# PCB_Blocks.net
KiCad netlist of a schematic drawn in Altium Designer
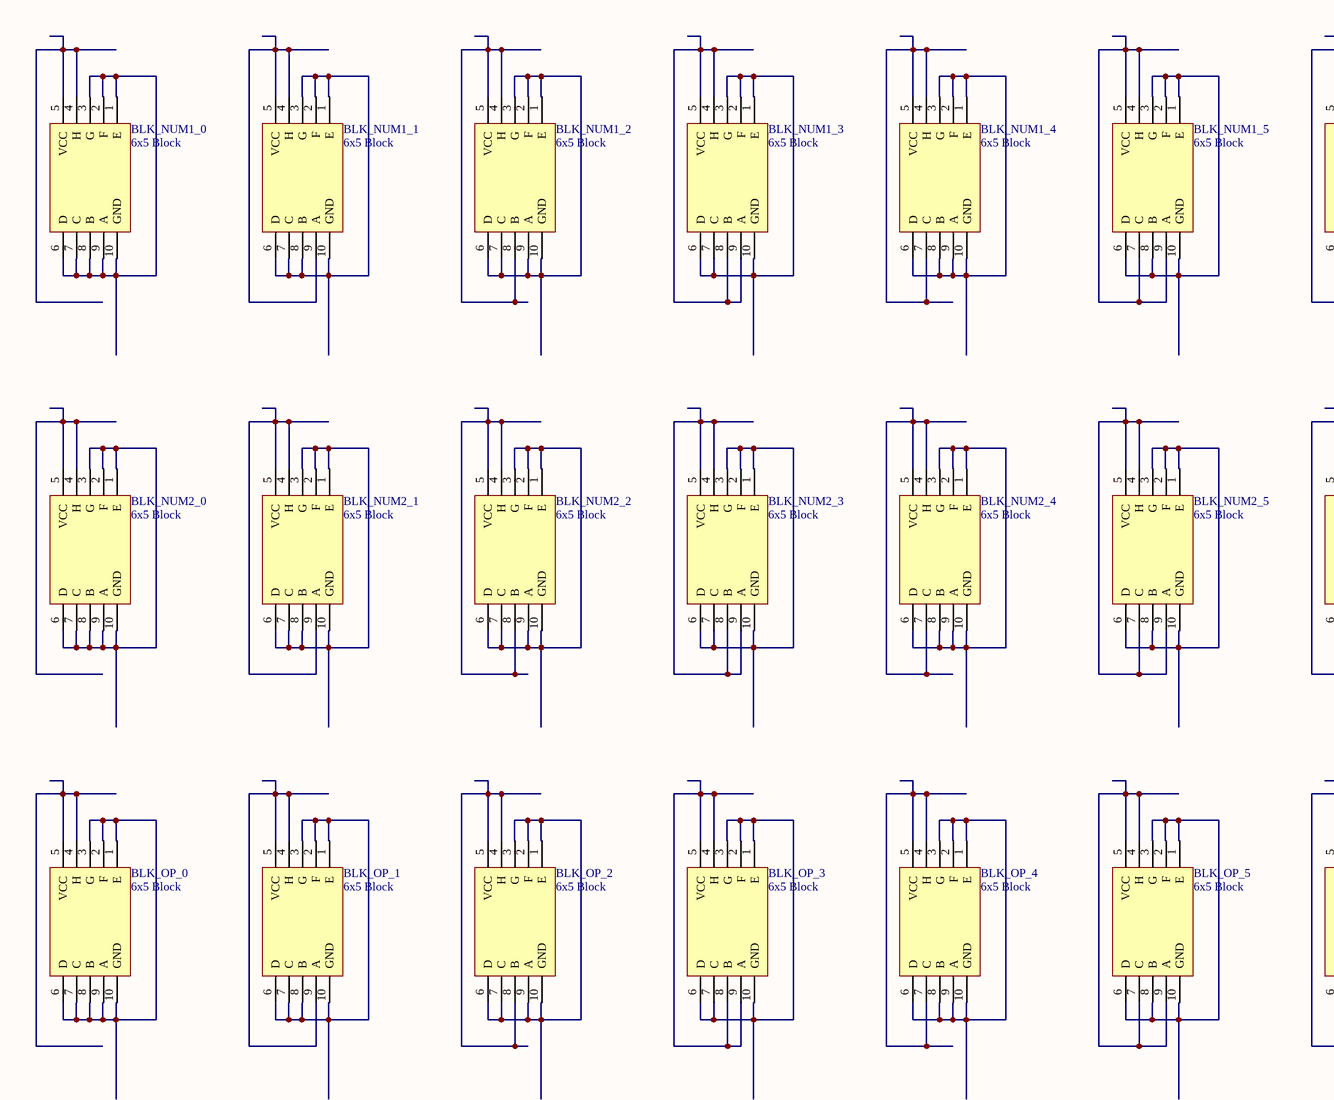
[diagram p0: PCB_Blocks.SchDoc, left]
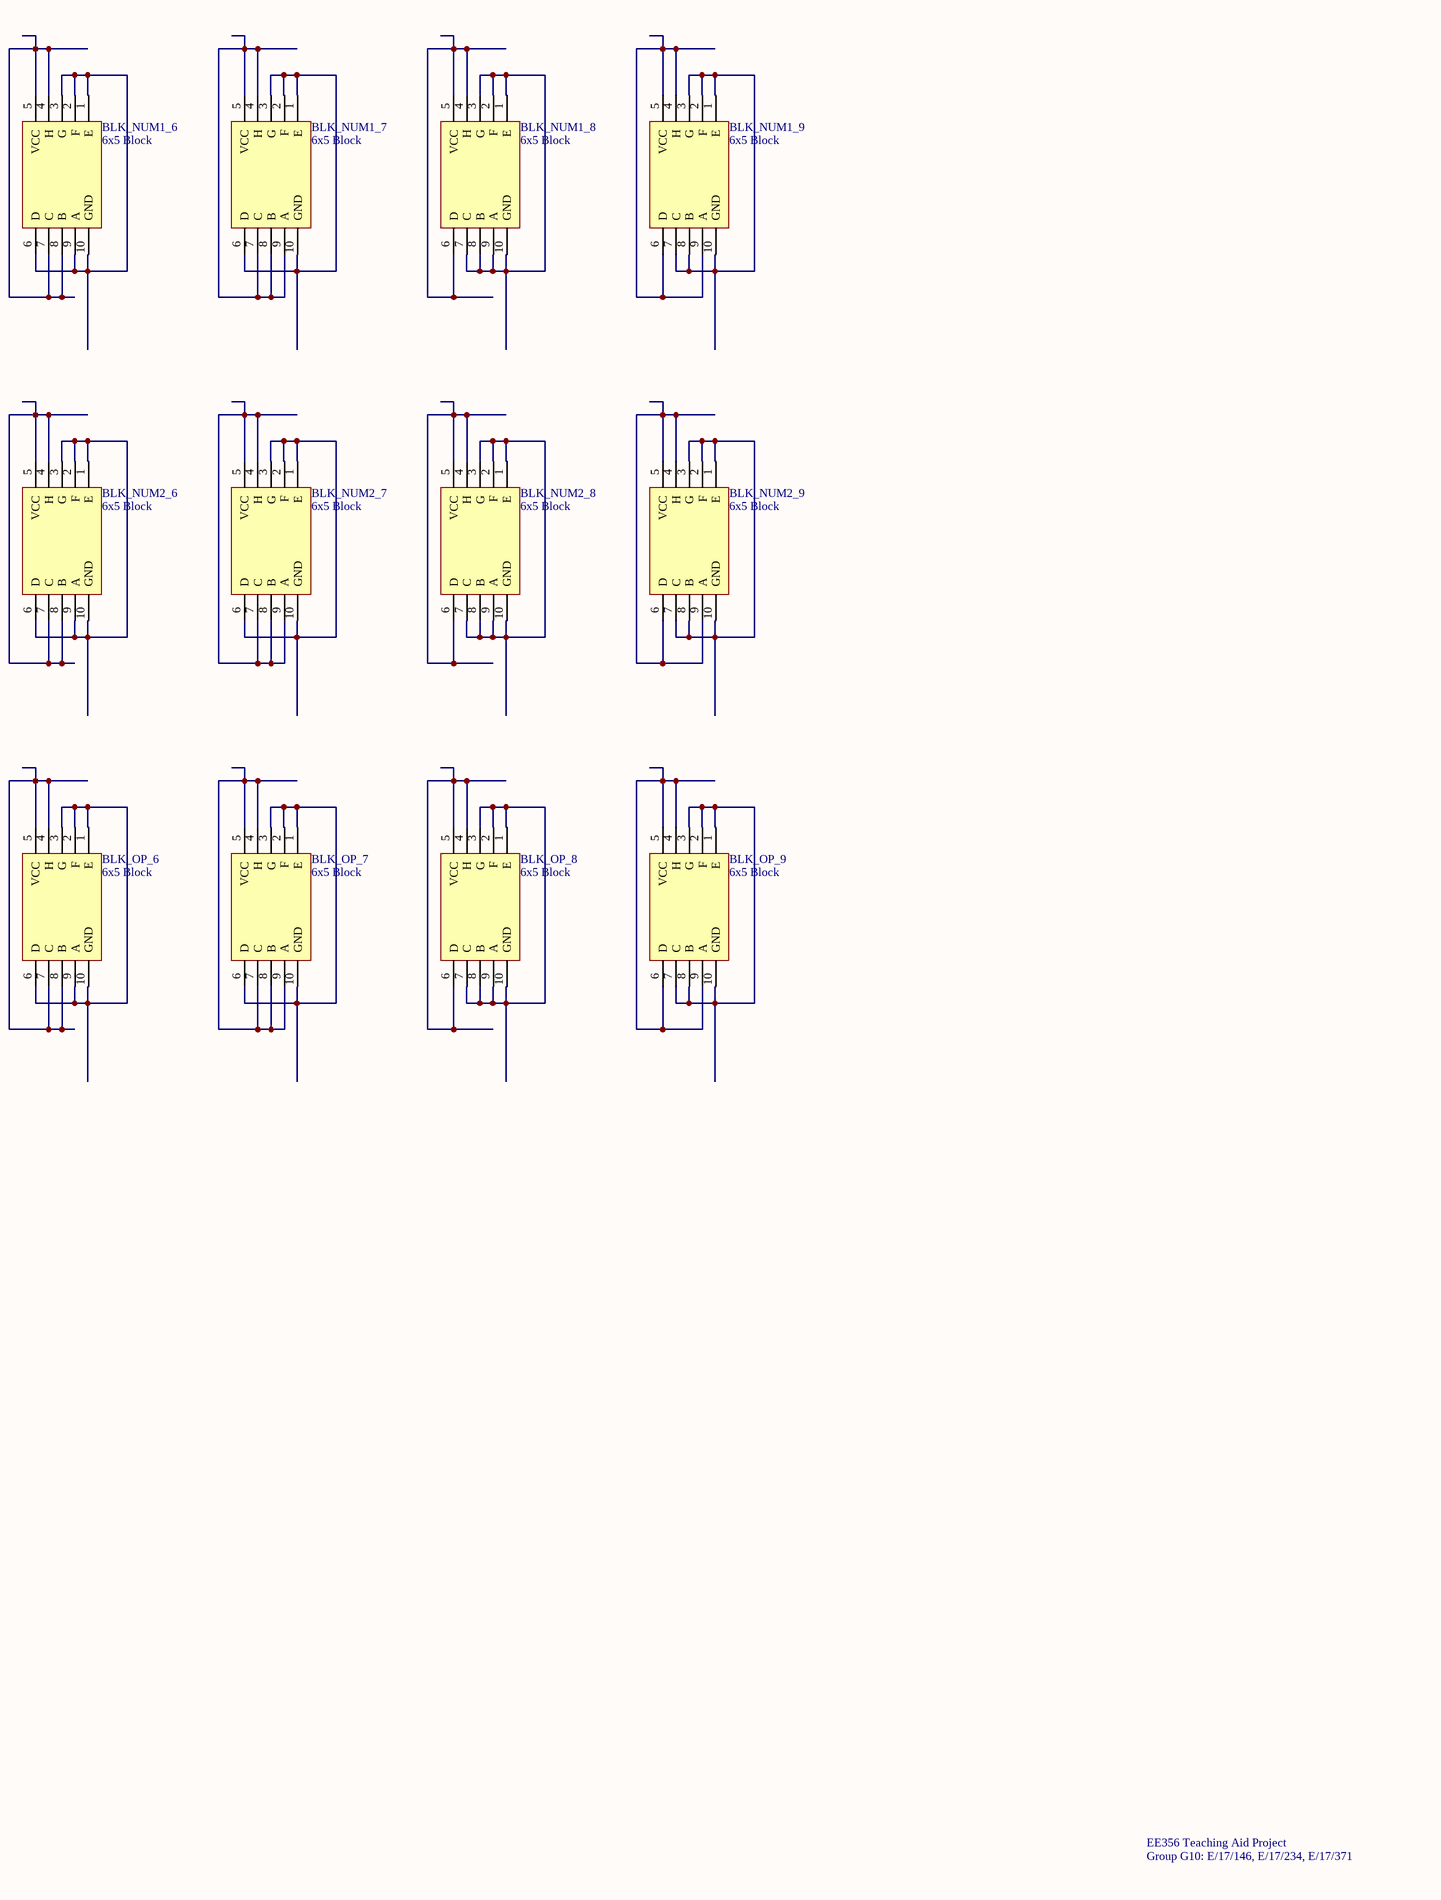
[diagram p1: PCB_Blocks.SchDoc, right]

(export (version "E")
  (design (tool "Eeschema 10.0.6"))
  (components
    (comp (ref "BLK_NUM1_0")
      (value "6x5 Block")
      (footprint "Block_6x5")
      (libsource (lib "Schlib1") (part "Block_6x5"))
    )
    (comp (ref "BLK_NUM1_1")
      (value "6x5 Block")
      (footprint "Block_6x5")
      (libsource (lib "Schlib1") (part "Block_6x5"))
    )
    (comp (ref "BLK_NUM1_2")
      (value "6x5 Block")
      (footprint "Block_6x5")
      (libsource (lib "Schlib1") (part "Block_6x5"))
    )
    (comp (ref "BLK_NUM1_3")
      (value "6x5 Block")
      (footprint "Block_6x5")
      (libsource (lib "Schlib1") (part "Block_6x5"))
    )
    (comp (ref "BLK_NUM1_4")
      (value "6x5 Block")
      (footprint "Block_6x5")
      (libsource (lib "Schlib1") (part "Block_6x5"))
    )
    (comp (ref "BLK_NUM1_5")
      (value "6x5 Block")
      (footprint "Block_6x5")
      (libsource (lib "Schlib1") (part "Block_6x5"))
    )
    (comp (ref "BLK_NUM1_6")
      (value "6x5 Block")
      (footprint "Block_6x5")
      (libsource (lib "Schlib1") (part "Block_6x5"))
    )
    (comp (ref "BLK_NUM1_7")
      (value "6x5 Block")
      (footprint "Block_6x5")
      (libsource (lib "Schlib1") (part "Block_6x5"))
    )
    (comp (ref "BLK_NUM1_8")
      (value "6x5 Block")
      (footprint "Block_6x5")
      (libsource (lib "Schlib1") (part "Block_6x5"))
    )
    (comp (ref "BLK_NUM1_9")
      (value "6x5 Block")
      (footprint "Block_6x5")
      (libsource (lib "Schlib1") (part "Block_6x5"))
    )
    (comp (ref "BLK_NUM2_0")
      (value "6x5 Block")
      (footprint "Block_6x5")
      (libsource (lib "Schlib1") (part "Block_6x5"))
    )
    (comp (ref "BLK_NUM2_1")
      (value "6x5 Block")
      (footprint "Block_6x5")
      (libsource (lib "Schlib1") (part "Block_6x5"))
    )
    (comp (ref "BLK_NUM2_2")
      (value "6x5 Block")
      (footprint "Block_6x5")
      (libsource (lib "Schlib1") (part "Block_6x5"))
    )
    (comp (ref "BLK_NUM2_3")
      (value "6x5 Block")
      (footprint "Block_6x5")
      (libsource (lib "Schlib1") (part "Block_6x5"))
    )
    (comp (ref "BLK_NUM2_4")
      (value "6x5 Block")
      (footprint "Block_6x5")
      (libsource (lib "Schlib1") (part "Block_6x5"))
    )
    (comp (ref "BLK_NUM2_5")
      (value "6x5 Block")
      (footprint "Block_6x5")
      (libsource (lib "Schlib1") (part "Block_6x5"))
    )
    (comp (ref "BLK_NUM2_6")
      (value "6x5 Block")
      (footprint "Block_6x5")
      (libsource (lib "Schlib1") (part "Block_6x5"))
    )
    (comp (ref "BLK_NUM2_7")
      (value "6x5 Block")
      (footprint "Block_6x5")
      (libsource (lib "Schlib1") (part "Block_6x5"))
    )
    (comp (ref "BLK_NUM2_8")
      (value "6x5 Block")
      (footprint "Block_6x5")
      (libsource (lib "Schlib1") (part "Block_6x5"))
    )
    (comp (ref "BLK_NUM2_9")
      (value "6x5 Block")
      (footprint "Block_6x5")
      (libsource (lib "Schlib1") (part "Block_6x5"))
    )
    (comp (ref "BLK_OP_0")
      (value "6x5 Block")
      (footprint "Block_6x5")
      (libsource (lib "Schlib1") (part "Block_6x5"))
    )
    (comp (ref "BLK_OP_1")
      (value "6x5 Block")
      (footprint "Block_6x5")
      (libsource (lib "Schlib1") (part "Block_6x5"))
    )
    (comp (ref "BLK_OP_2")
      (value "6x5 Block")
      (footprint "Block_6x5")
      (libsource (lib "Schlib1") (part "Block_6x5"))
    )
    (comp (ref "BLK_OP_3")
      (value "6x5 Block")
      (footprint "Block_6x5")
      (libsource (lib "Schlib1") (part "Block_6x5"))
    )
    (comp (ref "BLK_OP_4")
      (value "6x5 Block")
      (footprint "Block_6x5")
      (libsource (lib "Schlib1") (part "Block_6x5"))
    )
    (comp (ref "BLK_OP_5")
      (value "6x5 Block")
      (footprint "Block_6x5")
      (libsource (lib "Schlib1") (part "Block_6x5"))
    )
    (comp (ref "BLK_OP_6")
      (value "6x5 Block")
      (footprint "Block_6x5")
      (libsource (lib "Schlib1") (part "Block_6x5"))
    )
    (comp (ref "BLK_OP_7")
      (value "6x5 Block")
      (footprint "Block_6x5")
      (libsource (lib "Schlib1") (part "Block_6x5"))
    )
    (comp (ref "BLK_OP_8")
      (value "6x5 Block")
      (footprint "Block_6x5")
      (libsource (lib "Schlib1") (part "Block_6x5"))
    )
    (comp (ref "BLK_OP_9")
      (value "6x5 Block")
      (footprint "Block_6x5")
      (libsource (lib "Schlib1") (part "Block_6x5"))
    )
  )
  (nets
    (net (code "1") (name "Net-(BLK_NUM1_0-A)") (class "Default")
      (node (ref "BLK_NUM1_0") (pin "1") (pinfunction "E_1") (pintype "passive"))
      (node (ref "BLK_NUM1_0") (pin "10") (pinfunction "GND_10") (pintype "passive"))
      (node (ref "BLK_NUM1_0") (pin "2") (pinfunction "F_2") (pintype "passive"))
      (node (ref "BLK_NUM1_0") (pin "3") (pinfunction "G_3") (pintype "passive"))
      (node (ref "BLK_NUM1_0") (pin "6") (pinfunction "D_6") (pintype "passive"))
      (node (ref "BLK_NUM1_0") (pin "7") (pinfunction "C_7") (pintype "passive"))
      (node (ref "BLK_NUM1_0") (pin "8") (pinfunction "B_8") (pintype "passive"))
      (node (ref "BLK_NUM1_0") (pin "9") (pinfunction "A_9") (pintype "passive"))
    )
    (net (code "2") (name "Net-(BLK_NUM1_0-H)") (class "Default")
      (node (ref "BLK_NUM1_0") (pin "4") (pinfunction "H_4") (pintype "passive"))
      (node (ref "BLK_NUM1_0") (pin "5") (pinfunction "VCC_5") (pintype "passive"))
    )
    (net (code "3") (name "Net-(BLK_NUM1_1-A)") (class "Default")
      (node (ref "BLK_NUM1_1") (pin "4") (pinfunction "H_4") (pintype "passive"))
      (node (ref "BLK_NUM1_1") (pin "5") (pinfunction "VCC_5") (pintype "passive"))
      (node (ref "BLK_NUM1_1") (pin "9") (pinfunction "A_9") (pintype "passive"))
    )
    (net (code "4") (name "Net-(BLK_NUM1_1-B)") (class "Default")
      (node (ref "BLK_NUM1_1") (pin "1") (pinfunction "E_1") (pintype "passive"))
      (node (ref "BLK_NUM1_1") (pin "10") (pinfunction "GND_10") (pintype "passive"))
      (node (ref "BLK_NUM1_1") (pin "2") (pinfunction "F_2") (pintype "passive"))
      (node (ref "BLK_NUM1_1") (pin "3") (pinfunction "G_3") (pintype "passive"))
      (node (ref "BLK_NUM1_1") (pin "6") (pinfunction "D_6") (pintype "passive"))
      (node (ref "BLK_NUM1_1") (pin "7") (pinfunction "C_7") (pintype "passive"))
      (node (ref "BLK_NUM1_1") (pin "8") (pinfunction "B_8") (pintype "passive"))
    )
    (net (code "5") (name "Net-(BLK_NUM1_2-A)") (class "Default")
      (node (ref "BLK_NUM1_2") (pin "1") (pinfunction "E_1") (pintype "passive"))
      (node (ref "BLK_NUM1_2") (pin "10") (pinfunction "GND_10") (pintype "passive"))
      (node (ref "BLK_NUM1_2") (pin "2") (pinfunction "F_2") (pintype "passive"))
      (node (ref "BLK_NUM1_2") (pin "3") (pinfunction "G_3") (pintype "passive"))
      (node (ref "BLK_NUM1_2") (pin "6") (pinfunction "D_6") (pintype "passive"))
      (node (ref "BLK_NUM1_2") (pin "7") (pinfunction "C_7") (pintype "passive"))
      (node (ref "BLK_NUM1_2") (pin "9") (pinfunction "A_9") (pintype "passive"))
    )
    (net (code "6") (name "Net-(BLK_NUM1_2-B)") (class "Default")
      (node (ref "BLK_NUM1_2") (pin "4") (pinfunction "H_4") (pintype "passive"))
      (node (ref "BLK_NUM1_2") (pin "5") (pinfunction "VCC_5") (pintype "passive"))
      (node (ref "BLK_NUM1_2") (pin "8") (pinfunction "B_8") (pintype "passive"))
    )
    (net (code "7") (name "Net-(BLK_NUM1_3-A)") (class "Default")
      (node (ref "BLK_NUM1_3") (pin "4") (pinfunction "H_4") (pintype "passive"))
      (node (ref "BLK_NUM1_3") (pin "5") (pinfunction "VCC_5") (pintype "passive"))
      (node (ref "BLK_NUM1_3") (pin "8") (pinfunction "B_8") (pintype "passive"))
      (node (ref "BLK_NUM1_3") (pin "9") (pinfunction "A_9") (pintype "passive"))
    )
    (net (code "8") (name "Net-(BLK_NUM1_3-C)") (class "Default")
      (node (ref "BLK_NUM1_3") (pin "1") (pinfunction "E_1") (pintype "passive"))
      (node (ref "BLK_NUM1_3") (pin "10") (pinfunction "GND_10") (pintype "passive"))
      (node (ref "BLK_NUM1_3") (pin "2") (pinfunction "F_2") (pintype "passive"))
      (node (ref "BLK_NUM1_3") (pin "3") (pinfunction "G_3") (pintype "passive"))
      (node (ref "BLK_NUM1_3") (pin "6") (pinfunction "D_6") (pintype "passive"))
      (node (ref "BLK_NUM1_3") (pin "7") (pinfunction "C_7") (pintype "passive"))
    )
    (net (code "9") (name "Net-(BLK_NUM1_4-A)") (class "Default")
      (node (ref "BLK_NUM1_4") (pin "1") (pinfunction "E_1") (pintype "passive"))
      (node (ref "BLK_NUM1_4") (pin "10") (pinfunction "GND_10") (pintype "passive"))
      (node (ref "BLK_NUM1_4") (pin "2") (pinfunction "F_2") (pintype "passive"))
      (node (ref "BLK_NUM1_4") (pin "3") (pinfunction "G_3") (pintype "passive"))
      (node (ref "BLK_NUM1_4") (pin "6") (pinfunction "D_6") (pintype "passive"))
      (node (ref "BLK_NUM1_4") (pin "8") (pinfunction "B_8") (pintype "passive"))
      (node (ref "BLK_NUM1_4") (pin "9") (pinfunction "A_9") (pintype "passive"))
    )
    (net (code "10") (name "Net-(BLK_NUM1_4-C)") (class "Default")
      (node (ref "BLK_NUM1_4") (pin "4") (pinfunction "H_4") (pintype "passive"))
      (node (ref "BLK_NUM1_4") (pin "5") (pinfunction "VCC_5") (pintype "passive"))
      (node (ref "BLK_NUM1_4") (pin "7") (pinfunction "C_7") (pintype "passive"))
    )
    (net (code "11") (name "Net-(BLK_NUM1_5-A)") (class "Default")
      (node (ref "BLK_NUM1_5") (pin "4") (pinfunction "H_4") (pintype "passive"))
      (node (ref "BLK_NUM1_5") (pin "5") (pinfunction "VCC_5") (pintype "passive"))
      (node (ref "BLK_NUM1_5") (pin "7") (pinfunction "C_7") (pintype "passive"))
      (node (ref "BLK_NUM1_5") (pin "9") (pinfunction "A_9") (pintype "passive"))
    )
    (net (code "12") (name "Net-(BLK_NUM1_5-B)") (class "Default")
      (node (ref "BLK_NUM1_5") (pin "1") (pinfunction "E_1") (pintype "passive"))
      (node (ref "BLK_NUM1_5") (pin "10") (pinfunction "GND_10") (pintype "passive"))
      (node (ref "BLK_NUM1_5") (pin "2") (pinfunction "F_2") (pintype "passive"))
      (node (ref "BLK_NUM1_5") (pin "3") (pinfunction "G_3") (pintype "passive"))
      (node (ref "BLK_NUM1_5") (pin "6") (pinfunction "D_6") (pintype "passive"))
      (node (ref "BLK_NUM1_5") (pin "8") (pinfunction "B_8") (pintype "passive"))
    )
    (net (code "13") (name "Net-(BLK_NUM1_6-A)") (class "Default")
      (node (ref "BLK_NUM1_6") (pin "1") (pinfunction "E_1") (pintype "passive"))
      (node (ref "BLK_NUM1_6") (pin "10") (pinfunction "GND_10") (pintype "passive"))
      (node (ref "BLK_NUM1_6") (pin "2") (pinfunction "F_2") (pintype "passive"))
      (node (ref "BLK_NUM1_6") (pin "3") (pinfunction "G_3") (pintype "passive"))
      (node (ref "BLK_NUM1_6") (pin "6") (pinfunction "D_6") (pintype "passive"))
      (node (ref "BLK_NUM1_6") (pin "9") (pinfunction "A_9") (pintype "passive"))
    )
    (net (code "14") (name "Net-(BLK_NUM1_6-B)") (class "Default")
      (node (ref "BLK_NUM1_6") (pin "4") (pinfunction "H_4") (pintype "passive"))
      (node (ref "BLK_NUM1_6") (pin "5") (pinfunction "VCC_5") (pintype "passive"))
      (node (ref "BLK_NUM1_6") (pin "7") (pinfunction "C_7") (pintype "passive"))
      (node (ref "BLK_NUM1_6") (pin "8") (pinfunction "B_8") (pintype "passive"))
    )
    (net (code "15") (name "Net-(BLK_NUM1_7-A)") (class "Default")
      (node (ref "BLK_NUM1_7") (pin "4") (pinfunction "H_4") (pintype "passive"))
      (node (ref "BLK_NUM1_7") (pin "5") (pinfunction "VCC_5") (pintype "passive"))
      (node (ref "BLK_NUM1_7") (pin "7") (pinfunction "C_7") (pintype "passive"))
      (node (ref "BLK_NUM1_7") (pin "8") (pinfunction "B_8") (pintype "passive"))
      (node (ref "BLK_NUM1_7") (pin "9") (pinfunction "A_9") (pintype "passive"))
    )
    (net (code "16") (name "Net-(BLK_NUM1_7-D)") (class "Default")
      (node (ref "BLK_NUM1_7") (pin "1") (pinfunction "E_1") (pintype "passive"))
      (node (ref "BLK_NUM1_7") (pin "10") (pinfunction "GND_10") (pintype "passive"))
      (node (ref "BLK_NUM1_7") (pin "2") (pinfunction "F_2") (pintype "passive"))
      (node (ref "BLK_NUM1_7") (pin "3") (pinfunction "G_3") (pintype "passive"))
      (node (ref "BLK_NUM1_7") (pin "6") (pinfunction "D_6") (pintype "passive"))
    )
    (net (code "17") (name "Net-(BLK_NUM1_8-A)") (class "Default")
      (node (ref "BLK_NUM1_8") (pin "1") (pinfunction "E_1") (pintype "passive"))
      (node (ref "BLK_NUM1_8") (pin "10") (pinfunction "GND_10") (pintype "passive"))
      (node (ref "BLK_NUM1_8") (pin "2") (pinfunction "F_2") (pintype "passive"))
      (node (ref "BLK_NUM1_8") (pin "3") (pinfunction "G_3") (pintype "passive"))
      (node (ref "BLK_NUM1_8") (pin "7") (pinfunction "C_7") (pintype "passive"))
      (node (ref "BLK_NUM1_8") (pin "8") (pinfunction "B_8") (pintype "passive"))
      (node (ref "BLK_NUM1_8") (pin "9") (pinfunction "A_9") (pintype "passive"))
    )
    (net (code "18") (name "Net-(BLK_NUM1_8-D)") (class "Default")
      (node (ref "BLK_NUM1_8") (pin "4") (pinfunction "H_4") (pintype "passive"))
      (node (ref "BLK_NUM1_8") (pin "5") (pinfunction "VCC_5") (pintype "passive"))
      (node (ref "BLK_NUM1_8") (pin "6") (pinfunction "D_6") (pintype "passive"))
    )
    (net (code "19") (name "Net-(BLK_NUM1_9-A)") (class "Default")
      (node (ref "BLK_NUM1_9") (pin "4") (pinfunction "H_4") (pintype "passive"))
      (node (ref "BLK_NUM1_9") (pin "5") (pinfunction "VCC_5") (pintype "passive"))
      (node (ref "BLK_NUM1_9") (pin "6") (pinfunction "D_6") (pintype "passive"))
      (node (ref "BLK_NUM1_9") (pin "9") (pinfunction "A_9") (pintype "passive"))
    )
    (net (code "20") (name "Net-(BLK_NUM1_9-B)") (class "Default")
      (node (ref "BLK_NUM1_9") (pin "1") (pinfunction "E_1") (pintype "passive"))
      (node (ref "BLK_NUM1_9") (pin "10") (pinfunction "GND_10") (pintype "passive"))
      (node (ref "BLK_NUM1_9") (pin "2") (pinfunction "F_2") (pintype "passive"))
      (node (ref "BLK_NUM1_9") (pin "3") (pinfunction "G_3") (pintype "passive"))
      (node (ref "BLK_NUM1_9") (pin "7") (pinfunction "C_7") (pintype "passive"))
      (node (ref "BLK_NUM1_9") (pin "8") (pinfunction "B_8") (pintype "passive"))
    )
    (net (code "21") (name "Net-(BLK_NUM2_0-A)") (class "Default")
      (node (ref "BLK_NUM2_0") (pin "1") (pinfunction "E_1") (pintype "passive"))
      (node (ref "BLK_NUM2_0") (pin "10") (pinfunction "GND_10") (pintype "passive"))
      (node (ref "BLK_NUM2_0") (pin "2") (pinfunction "F_2") (pintype "passive"))
      (node (ref "BLK_NUM2_0") (pin "3") (pinfunction "G_3") (pintype "passive"))
      (node (ref "BLK_NUM2_0") (pin "6") (pinfunction "D_6") (pintype "passive"))
      (node (ref "BLK_NUM2_0") (pin "7") (pinfunction "C_7") (pintype "passive"))
      (node (ref "BLK_NUM2_0") (pin "8") (pinfunction "B_8") (pintype "passive"))
      (node (ref "BLK_NUM2_0") (pin "9") (pinfunction "A_9") (pintype "passive"))
    )
    (net (code "22") (name "Net-(BLK_NUM2_0-H)") (class "Default")
      (node (ref "BLK_NUM2_0") (pin "4") (pinfunction "H_4") (pintype "passive"))
      (node (ref "BLK_NUM2_0") (pin "5") (pinfunction "VCC_5") (pintype "passive"))
    )
    (net (code "23") (name "Net-(BLK_NUM2_1-A)") (class "Default")
      (node (ref "BLK_NUM2_1") (pin "4") (pinfunction "H_4") (pintype "passive"))
      (node (ref "BLK_NUM2_1") (pin "5") (pinfunction "VCC_5") (pintype "passive"))
      (node (ref "BLK_NUM2_1") (pin "9") (pinfunction "A_9") (pintype "passive"))
    )
    (net (code "24") (name "Net-(BLK_NUM2_1-B)") (class "Default")
      (node (ref "BLK_NUM2_1") (pin "1") (pinfunction "E_1") (pintype "passive"))
      (node (ref "BLK_NUM2_1") (pin "10") (pinfunction "GND_10") (pintype "passive"))
      (node (ref "BLK_NUM2_1") (pin "2") (pinfunction "F_2") (pintype "passive"))
      (node (ref "BLK_NUM2_1") (pin "3") (pinfunction "G_3") (pintype "passive"))
      (node (ref "BLK_NUM2_1") (pin "6") (pinfunction "D_6") (pintype "passive"))
      (node (ref "BLK_NUM2_1") (pin "7") (pinfunction "C_7") (pintype "passive"))
      (node (ref "BLK_NUM2_1") (pin "8") (pinfunction "B_8") (pintype "passive"))
    )
    (net (code "25") (name "Net-(BLK_NUM2_2-A)") (class "Default")
      (node (ref "BLK_NUM2_2") (pin "1") (pinfunction "E_1") (pintype "passive"))
      (node (ref "BLK_NUM2_2") (pin "10") (pinfunction "GND_10") (pintype "passive"))
      (node (ref "BLK_NUM2_2") (pin "2") (pinfunction "F_2") (pintype "passive"))
      (node (ref "BLK_NUM2_2") (pin "3") (pinfunction "G_3") (pintype "passive"))
      (node (ref "BLK_NUM2_2") (pin "6") (pinfunction "D_6") (pintype "passive"))
      (node (ref "BLK_NUM2_2") (pin "7") (pinfunction "C_7") (pintype "passive"))
      (node (ref "BLK_NUM2_2") (pin "9") (pinfunction "A_9") (pintype "passive"))
    )
    (net (code "26") (name "Net-(BLK_NUM2_2-B)") (class "Default")
      (node (ref "BLK_NUM2_2") (pin "4") (pinfunction "H_4") (pintype "passive"))
      (node (ref "BLK_NUM2_2") (pin "5") (pinfunction "VCC_5") (pintype "passive"))
      (node (ref "BLK_NUM2_2") (pin "8") (pinfunction "B_8") (pintype "passive"))
    )
    (net (code "27") (name "Net-(BLK_NUM2_3-A)") (class "Default")
      (node (ref "BLK_NUM2_3") (pin "4") (pinfunction "H_4") (pintype "passive"))
      (node (ref "BLK_NUM2_3") (pin "5") (pinfunction "VCC_5") (pintype "passive"))
      (node (ref "BLK_NUM2_3") (pin "8") (pinfunction "B_8") (pintype "passive"))
      (node (ref "BLK_NUM2_3") (pin "9") (pinfunction "A_9") (pintype "passive"))
    )
    (net (code "28") (name "Net-(BLK_NUM2_3-C)") (class "Default")
      (node (ref "BLK_NUM2_3") (pin "1") (pinfunction "E_1") (pintype "passive"))
      (node (ref "BLK_NUM2_3") (pin "10") (pinfunction "GND_10") (pintype "passive"))
      (node (ref "BLK_NUM2_3") (pin "2") (pinfunction "F_2") (pintype "passive"))
      (node (ref "BLK_NUM2_3") (pin "3") (pinfunction "G_3") (pintype "passive"))
      (node (ref "BLK_NUM2_3") (pin "6") (pinfunction "D_6") (pintype "passive"))
      (node (ref "BLK_NUM2_3") (pin "7") (pinfunction "C_7") (pintype "passive"))
    )
    (net (code "29") (name "Net-(BLK_NUM2_4-A)") (class "Default")
      (node (ref "BLK_NUM2_4") (pin "1") (pinfunction "E_1") (pintype "passive"))
      (node (ref "BLK_NUM2_4") (pin "10") (pinfunction "GND_10") (pintype "passive"))
      (node (ref "BLK_NUM2_4") (pin "2") (pinfunction "F_2") (pintype "passive"))
      (node (ref "BLK_NUM2_4") (pin "3") (pinfunction "G_3") (pintype "passive"))
      (node (ref "BLK_NUM2_4") (pin "6") (pinfunction "D_6") (pintype "passive"))
      (node (ref "BLK_NUM2_4") (pin "8") (pinfunction "B_8") (pintype "passive"))
      (node (ref "BLK_NUM2_4") (pin "9") (pinfunction "A_9") (pintype "passive"))
    )
    (net (code "30") (name "Net-(BLK_NUM2_4-C)") (class "Default")
      (node (ref "BLK_NUM2_4") (pin "4") (pinfunction "H_4") (pintype "passive"))
      (node (ref "BLK_NUM2_4") (pin "5") (pinfunction "VCC_5") (pintype "passive"))
      (node (ref "BLK_NUM2_4") (pin "7") (pinfunction "C_7") (pintype "passive"))
    )
    (net (code "31") (name "Net-(BLK_NUM2_5-A)") (class "Default")
      (node (ref "BLK_NUM2_5") (pin "4") (pinfunction "H_4") (pintype "passive"))
      (node (ref "BLK_NUM2_5") (pin "5") (pinfunction "VCC_5") (pintype "passive"))
      (node (ref "BLK_NUM2_5") (pin "7") (pinfunction "C_7") (pintype "passive"))
      (node (ref "BLK_NUM2_5") (pin "9") (pinfunction "A_9") (pintype "passive"))
    )
    (net (code "32") (name "Net-(BLK_NUM2_5-B)") (class "Default")
      (node (ref "BLK_NUM2_5") (pin "1") (pinfunction "E_1") (pintype "passive"))
      (node (ref "BLK_NUM2_5") (pin "10") (pinfunction "GND_10") (pintype "passive"))
      (node (ref "BLK_NUM2_5") (pin "2") (pinfunction "F_2") (pintype "passive"))
      (node (ref "BLK_NUM2_5") (pin "3") (pinfunction "G_3") (pintype "passive"))
      (node (ref "BLK_NUM2_5") (pin "6") (pinfunction "D_6") (pintype "passive"))
      (node (ref "BLK_NUM2_5") (pin "8") (pinfunction "B_8") (pintype "passive"))
    )
    (net (code "33") (name "Net-(BLK_NUM2_6-A)") (class "Default")
      (node (ref "BLK_NUM2_6") (pin "1") (pinfunction "E_1") (pintype "passive"))
      (node (ref "BLK_NUM2_6") (pin "10") (pinfunction "GND_10") (pintype "passive"))
      (node (ref "BLK_NUM2_6") (pin "2") (pinfunction "F_2") (pintype "passive"))
      (node (ref "BLK_NUM2_6") (pin "3") (pinfunction "G_3") (pintype "passive"))
      (node (ref "BLK_NUM2_6") (pin "6") (pinfunction "D_6") (pintype "passive"))
      (node (ref "BLK_NUM2_6") (pin "9") (pinfunction "A_9") (pintype "passive"))
    )
    (net (code "34") (name "Net-(BLK_NUM2_6-B)") (class "Default")
      (node (ref "BLK_NUM2_6") (pin "4") (pinfunction "H_4") (pintype "passive"))
      (node (ref "BLK_NUM2_6") (pin "5") (pinfunction "VCC_5") (pintype "passive"))
      (node (ref "BLK_NUM2_6") (pin "7") (pinfunction "C_7") (pintype "passive"))
      (node (ref "BLK_NUM2_6") (pin "8") (pinfunction "B_8") (pintype "passive"))
    )
    (net (code "35") (name "Net-(BLK_NUM2_7-A)") (class "Default")
      (node (ref "BLK_NUM2_7") (pin "4") (pinfunction "H_4") (pintype "passive"))
      (node (ref "BLK_NUM2_7") (pin "5") (pinfunction "VCC_5") (pintype "passive"))
      (node (ref "BLK_NUM2_7") (pin "7") (pinfunction "C_7") (pintype "passive"))
      (node (ref "BLK_NUM2_7") (pin "8") (pinfunction "B_8") (pintype "passive"))
      (node (ref "BLK_NUM2_7") (pin "9") (pinfunction "A_9") (pintype "passive"))
    )
    (net (code "36") (name "Net-(BLK_NUM2_7-D)") (class "Default")
      (node (ref "BLK_NUM2_7") (pin "1") (pinfunction "E_1") (pintype "passive"))
      (node (ref "BLK_NUM2_7") (pin "10") (pinfunction "GND_10") (pintype "passive"))
      (node (ref "BLK_NUM2_7") (pin "2") (pinfunction "F_2") (pintype "passive"))
      (node (ref "BLK_NUM2_7") (pin "3") (pinfunction "G_3") (pintype "passive"))
      (node (ref "BLK_NUM2_7") (pin "6") (pinfunction "D_6") (pintype "passive"))
    )
    (net (code "37") (name "Net-(BLK_NUM2_8-A)") (class "Default")
      (node (ref "BLK_NUM2_8") (pin "1") (pinfunction "E_1") (pintype "passive"))
      (node (ref "BLK_NUM2_8") (pin "10") (pinfunction "GND_10") (pintype "passive"))
      (node (ref "BLK_NUM2_8") (pin "2") (pinfunction "F_2") (pintype "passive"))
      (node (ref "BLK_NUM2_8") (pin "3") (pinfunction "G_3") (pintype "passive"))
      (node (ref "BLK_NUM2_8") (pin "7") (pinfunction "C_7") (pintype "passive"))
      (node (ref "BLK_NUM2_8") (pin "8") (pinfunction "B_8") (pintype "passive"))
      (node (ref "BLK_NUM2_8") (pin "9") (pinfunction "A_9") (pintype "passive"))
    )
    (net (code "38") (name "Net-(BLK_NUM2_8-D)") (class "Default")
      (node (ref "BLK_NUM2_8") (pin "4") (pinfunction "H_4") (pintype "passive"))
      (node (ref "BLK_NUM2_8") (pin "5") (pinfunction "VCC_5") (pintype "passive"))
      (node (ref "BLK_NUM2_8") (pin "6") (pinfunction "D_6") (pintype "passive"))
    )
    (net (code "39") (name "Net-(BLK_NUM2_9-A)") (class "Default")
      (node (ref "BLK_NUM2_9") (pin "4") (pinfunction "H_4") (pintype "passive"))
      (node (ref "BLK_NUM2_9") (pin "5") (pinfunction "VCC_5") (pintype "passive"))
      (node (ref "BLK_NUM2_9") (pin "6") (pinfunction "D_6") (pintype "passive"))
      (node (ref "BLK_NUM2_9") (pin "9") (pinfunction "A_9") (pintype "passive"))
    )
    (net (code "40") (name "Net-(BLK_NUM2_9-B)") (class "Default")
      (node (ref "BLK_NUM2_9") (pin "1") (pinfunction "E_1") (pintype "passive"))
      (node (ref "BLK_NUM2_9") (pin "10") (pinfunction "GND_10") (pintype "passive"))
      (node (ref "BLK_NUM2_9") (pin "2") (pinfunction "F_2") (pintype "passive"))
      (node (ref "BLK_NUM2_9") (pin "3") (pinfunction "G_3") (pintype "passive"))
      (node (ref "BLK_NUM2_9") (pin "7") (pinfunction "C_7") (pintype "passive"))
      (node (ref "BLK_NUM2_9") (pin "8") (pinfunction "B_8") (pintype "passive"))
    )
    (net (code "41") (name "Net-(BLK_OP_0-A)") (class "Default")
      (node (ref "BLK_OP_0") (pin "1") (pinfunction "E_1") (pintype "passive"))
      (node (ref "BLK_OP_0") (pin "10") (pinfunction "GND_10") (pintype "passive"))
      (node (ref "BLK_OP_0") (pin "2") (pinfunction "F_2") (pintype "passive"))
      (node (ref "BLK_OP_0") (pin "3") (pinfunction "G_3") (pintype "passive"))
      (node (ref "BLK_OP_0") (pin "6") (pinfunction "D_6") (pintype "passive"))
      (node (ref "BLK_OP_0") (pin "7") (pinfunction "C_7") (pintype "passive"))
      (node (ref "BLK_OP_0") (pin "8") (pinfunction "B_8") (pintype "passive"))
      (node (ref "BLK_OP_0") (pin "9") (pinfunction "A_9") (pintype "passive"))
    )
    (net (code "42") (name "Net-(BLK_OP_0-H)") (class "Default")
      (node (ref "BLK_OP_0") (pin "4") (pinfunction "H_4") (pintype "passive"))
      (node (ref "BLK_OP_0") (pin "5") (pinfunction "VCC_5") (pintype "passive"))
    )
    (net (code "43") (name "Net-(BLK_OP_1-A)") (class "Default")
      (node (ref "BLK_OP_1") (pin "4") (pinfunction "H_4") (pintype "passive"))
      (node (ref "BLK_OP_1") (pin "5") (pinfunction "VCC_5") (pintype "passive"))
      (node (ref "BLK_OP_1") (pin "9") (pinfunction "A_9") (pintype "passive"))
    )
    (net (code "44") (name "Net-(BLK_OP_1-B)") (class "Default")
      (node (ref "BLK_OP_1") (pin "1") (pinfunction "E_1") (pintype "passive"))
      (node (ref "BLK_OP_1") (pin "10") (pinfunction "GND_10") (pintype "passive"))
      (node (ref "BLK_OP_1") (pin "2") (pinfunction "F_2") (pintype "passive"))
      (node (ref "BLK_OP_1") (pin "3") (pinfunction "G_3") (pintype "passive"))
      (node (ref "BLK_OP_1") (pin "6") (pinfunction "D_6") (pintype "passive"))
      (node (ref "BLK_OP_1") (pin "7") (pinfunction "C_7") (pintype "passive"))
      (node (ref "BLK_OP_1") (pin "8") (pinfunction "B_8") (pintype "passive"))
    )
    (net (code "45") (name "Net-(BLK_OP_2-A)") (class "Default")
      (node (ref "BLK_OP_2") (pin "1") (pinfunction "E_1") (pintype "passive"))
      (node (ref "BLK_OP_2") (pin "10") (pinfunction "GND_10") (pintype "passive"))
      (node (ref "BLK_OP_2") (pin "2") (pinfunction "F_2") (pintype "passive"))
      (node (ref "BLK_OP_2") (pin "3") (pinfunction "G_3") (pintype "passive"))
      (node (ref "BLK_OP_2") (pin "6") (pinfunction "D_6") (pintype "passive"))
      (node (ref "BLK_OP_2") (pin "7") (pinfunction "C_7") (pintype "passive"))
      (node (ref "BLK_OP_2") (pin "9") (pinfunction "A_9") (pintype "passive"))
    )
    (net (code "46") (name "Net-(BLK_OP_2-B)") (class "Default")
      (node (ref "BLK_OP_2") (pin "4") (pinfunction "H_4") (pintype "passive"))
      (node (ref "BLK_OP_2") (pin "5") (pinfunction "VCC_5") (pintype "passive"))
      (node (ref "BLK_OP_2") (pin "8") (pinfunction "B_8") (pintype "passive"))
    )
    (net (code "47") (name "Net-(BLK_OP_3-A)") (class "Default")
      (node (ref "BLK_OP_3") (pin "4") (pinfunction "H_4") (pintype "passive"))
      (node (ref "BLK_OP_3") (pin "5") (pinfunction "VCC_5") (pintype "passive"))
      (node (ref "BLK_OP_3") (pin "8") (pinfunction "B_8") (pintype "passive"))
      (node (ref "BLK_OP_3") (pin "9") (pinfunction "A_9") (pintype "passive"))
    )
    (net (code "48") (name "Net-(BLK_OP_3-C)") (class "Default")
      (node (ref "BLK_OP_3") (pin "1") (pinfunction "E_1") (pintype "passive"))
      (node (ref "BLK_OP_3") (pin "10") (pinfunction "GND_10") (pintype "passive"))
      (node (ref "BLK_OP_3") (pin "2") (pinfunction "F_2") (pintype "passive"))
      (node (ref "BLK_OP_3") (pin "3") (pinfunction "G_3") (pintype "passive"))
      (node (ref "BLK_OP_3") (pin "6") (pinfunction "D_6") (pintype "passive"))
      (node (ref "BLK_OP_3") (pin "7") (pinfunction "C_7") (pintype "passive"))
    )
    (net (code "49") (name "Net-(BLK_OP_4-A)") (class "Default")
      (node (ref "BLK_OP_4") (pin "1") (pinfunction "E_1") (pintype "passive"))
      (node (ref "BLK_OP_4") (pin "10") (pinfunction "GND_10") (pintype "passive"))
      (node (ref "BLK_OP_4") (pin "2") (pinfunction "F_2") (pintype "passive"))
      (node (ref "BLK_OP_4") (pin "3") (pinfunction "G_3") (pintype "passive"))
      (node (ref "BLK_OP_4") (pin "6") (pinfunction "D_6") (pintype "passive"))
      (node (ref "BLK_OP_4") (pin "8") (pinfunction "B_8") (pintype "passive"))
      (node (ref "BLK_OP_4") (pin "9") (pinfunction "A_9") (pintype "passive"))
    )
    (net (code "50") (name "Net-(BLK_OP_4-C)") (class "Default")
      (node (ref "BLK_OP_4") (pin "4") (pinfunction "H_4") (pintype "passive"))
      (node (ref "BLK_OP_4") (pin "5") (pinfunction "VCC_5") (pintype "passive"))
      (node (ref "BLK_OP_4") (pin "7") (pinfunction "C_7") (pintype "passive"))
    )
    (net (code "51") (name "Net-(BLK_OP_5-A)") (class "Default")
      (node (ref "BLK_OP_5") (pin "4") (pinfunction "H_4") (pintype "passive"))
      (node (ref "BLK_OP_5") (pin "5") (pinfunction "VCC_5") (pintype "passive"))
      (node (ref "BLK_OP_5") (pin "7") (pinfunction "C_7") (pintype "passive"))
      (node (ref "BLK_OP_5") (pin "9") (pinfunction "A_9") (pintype "passive"))
    )
    (net (code "52") (name "Net-(BLK_OP_5-B)") (class "Default")
      (node (ref "BLK_OP_5") (pin "1") (pinfunction "E_1") (pintype "passive"))
      (node (ref "BLK_OP_5") (pin "10") (pinfunction "GND_10") (pintype "passive"))
      (node (ref "BLK_OP_5") (pin "2") (pinfunction "F_2") (pintype "passive"))
      (node (ref "BLK_OP_5") (pin "3") (pinfunction "G_3") (pintype "passive"))
      (node (ref "BLK_OP_5") (pin "6") (pinfunction "D_6") (pintype "passive"))
      (node (ref "BLK_OP_5") (pin "8") (pinfunction "B_8") (pintype "passive"))
    )
    (net (code "53") (name "Net-(BLK_OP_6-A)") (class "Default")
      (node (ref "BLK_OP_6") (pin "1") (pinfunction "E_1") (pintype "passive"))
      (node (ref "BLK_OP_6") (pin "10") (pinfunction "GND_10") (pintype "passive"))
      (node (ref "BLK_OP_6") (pin "2") (pinfunction "F_2") (pintype "passive"))
      (node (ref "BLK_OP_6") (pin "3") (pinfunction "G_3") (pintype "passive"))
      (node (ref "BLK_OP_6") (pin "6") (pinfunction "D_6") (pintype "passive"))
      (node (ref "BLK_OP_6") (pin "9") (pinfunction "A_9") (pintype "passive"))
    )
    (net (code "54") (name "Net-(BLK_OP_6-B)") (class "Default")
      (node (ref "BLK_OP_6") (pin "4") (pinfunction "H_4") (pintype "passive"))
      (node (ref "BLK_OP_6") (pin "5") (pinfunction "VCC_5") (pintype "passive"))
      (node (ref "BLK_OP_6") (pin "7") (pinfunction "C_7") (pintype "passive"))
      (node (ref "BLK_OP_6") (pin "8") (pinfunction "B_8") (pintype "passive"))
    )
    (net (code "55") (name "Net-(BLK_OP_7-A)") (class "Default")
      (node (ref "BLK_OP_7") (pin "4") (pinfunction "H_4") (pintype "passive"))
      (node (ref "BLK_OP_7") (pin "5") (pinfunction "VCC_5") (pintype "passive"))
      (node (ref "BLK_OP_7") (pin "7") (pinfunction "C_7") (pintype "passive"))
      (node (ref "BLK_OP_7") (pin "8") (pinfunction "B_8") (pintype "passive"))
      (node (ref "BLK_OP_7") (pin "9") (pinfunction "A_9") (pintype "passive"))
    )
    (net (code "56") (name "Net-(BLK_OP_7-D)") (class "Default")
      (node (ref "BLK_OP_7") (pin "1") (pinfunction "E_1") (pintype "passive"))
      (node (ref "BLK_OP_7") (pin "10") (pinfunction "GND_10") (pintype "passive"))
      (node (ref "BLK_OP_7") (pin "2") (pinfunction "F_2") (pintype "passive"))
      (node (ref "BLK_OP_7") (pin "3") (pinfunction "G_3") (pintype "passive"))
      (node (ref "BLK_OP_7") (pin "6") (pinfunction "D_6") (pintype "passive"))
    )
    (net (code "57") (name "Net-(BLK_OP_8-A)") (class "Default")
      (node (ref "BLK_OP_8") (pin "1") (pinfunction "E_1") (pintype "passive"))
      (node (ref "BLK_OP_8") (pin "10") (pinfunction "GND_10") (pintype "passive"))
      (node (ref "BLK_OP_8") (pin "2") (pinfunction "F_2") (pintype "passive"))
      (node (ref "BLK_OP_8") (pin "3") (pinfunction "G_3") (pintype "passive"))
      (node (ref "BLK_OP_8") (pin "7") (pinfunction "C_7") (pintype "passive"))
      (node (ref "BLK_OP_8") (pin "8") (pinfunction "B_8") (pintype "passive"))
      (node (ref "BLK_OP_8") (pin "9") (pinfunction "A_9") (pintype "passive"))
    )
    (net (code "58") (name "Net-(BLK_OP_8-D)") (class "Default")
      (node (ref "BLK_OP_8") (pin "4") (pinfunction "H_4") (pintype "passive"))
      (node (ref "BLK_OP_8") (pin "5") (pinfunction "VCC_5") (pintype "passive"))
      (node (ref "BLK_OP_8") (pin "6") (pinfunction "D_6") (pintype "passive"))
    )
    (net (code "59") (name "Net-(BLK_OP_9-A)") (class "Default")
      (node (ref "BLK_OP_9") (pin "4") (pinfunction "H_4") (pintype "passive"))
      (node (ref "BLK_OP_9") (pin "5") (pinfunction "VCC_5") (pintype "passive"))
      (node (ref "BLK_OP_9") (pin "6") (pinfunction "D_6") (pintype "passive"))
      (node (ref "BLK_OP_9") (pin "9") (pinfunction "A_9") (pintype "passive"))
    )
    (net (code "60") (name "Net-(BLK_OP_9-B)") (class "Default")
      (node (ref "BLK_OP_9") (pin "1") (pinfunction "E_1") (pintype "passive"))
      (node (ref "BLK_OP_9") (pin "10") (pinfunction "GND_10") (pintype "passive"))
      (node (ref "BLK_OP_9") (pin "2") (pinfunction "F_2") (pintype "passive"))
      (node (ref "BLK_OP_9") (pin "3") (pinfunction "G_3") (pintype "passive"))
      (node (ref "BLK_OP_9") (pin "7") (pinfunction "C_7") (pintype "passive"))
      (node (ref "BLK_OP_9") (pin "8") (pinfunction "B_8") (pintype "passive"))
    )
  )
)
